# CAAint.net
KiCad netlist of a schematic drawn in EAGLE
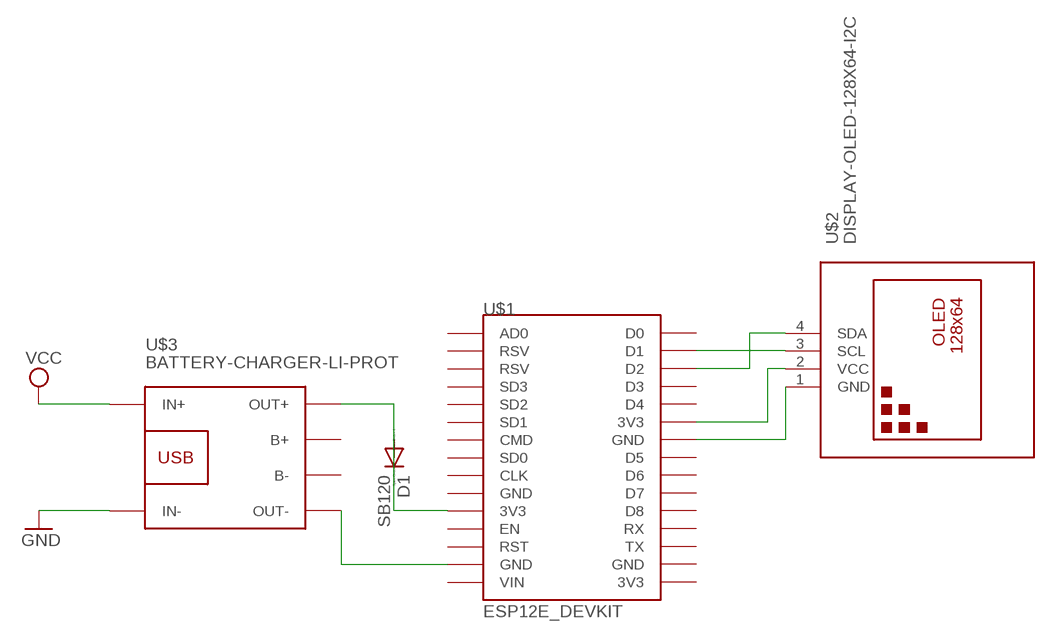
[diagram p0: schematic, sheet 1]

(export (version "E")
  (design (tool "Eeschema 10.0.6"))
  (components
    (comp (ref "D1")
      (value "SB120")
      (footprint "eagle-import:DO41-10")
      (libsource (lib "eagle-import") (part "SB120"))
    )
    (comp (ref "U$1")
      (value "ESP12E_DEVKIT")
      (footprint "eagle-import:ESP12E_DEVKIT")
      (libsource (lib "eagle-import") (part "ESP12E_DEVKIT"))
    )
    (comp (ref "U$2")
      (value "DISPLAY-OLED-128X64-I2C")
      (footprint "eagle-import:DISPLAY-OLED-128X64-I2C")
      (libsource (lib "eagle-import") (part "DISPLAY-OLED-128X64-I2C"))
    )
    (comp (ref "U$3")
      (value "BATTERY-CHARGER-LI-PROT")
      (footprint "eagle-import:BATTERY-CHARGER-LI-PROT")
      (libsource (lib "eagle-import") (part "BATTERY-CHARGER-LI-PROT"))
    )
  )
  (nets
    (net (code "1") (name "GND") (class "Default")
      (node (ref "U$1") (pin "GND@1") (pinfunction "GND_GND@1") (pintype "bidirectional"))
      (node (ref "U$1") (pin "GND@2") (pinfunction "GND_GND@2") (pintype "bidirectional"))
      (node (ref "U$2") (pin "1") (pinfunction "GND_1") (pintype "power_in"))
      (node (ref "U$3") (pin "IN-") (pinfunction "IN-_IN-") (pintype "bidirectional"))
      (node (ref "U$3") (pin "OUT-") (pinfunction "OUT-_OUT-") (pintype "bidirectional"))
    )
    (net (code "2") (name "Net-(D1-PadA)") (class "Default")
      (node (ref "D1") (pin "A") (pinfunction "A_A") (pintype "passive"))
      (node (ref "U$1") (pin "3V3@0") (pinfunction "3V3_3V3@0") (pintype "bidirectional"))
    )
    (net (code "3") (name "Net-(D1-PadC)") (class "Default")
      (node (ref "D1") (pin "C") (pinfunction "C_C") (pintype "passive"))
      (node (ref "U$3") (pin "OUT+") (pinfunction "OUT+_OUT+") (pintype "bidirectional"))
    )
    (net (code "4") (name "Net-(U$2-SCL)") (class "Default")
      (node (ref "U$1") (pin "D1") (pinfunction "D1_D1") (pintype "bidirectional"))
      (node (ref "U$2") (pin "3") (pinfunction "SCL_3") (pintype "bidirectional"))
    )
    (net (code "5") (name "Net-(U$2-SDA)") (class "Default")
      (node (ref "U$1") (pin "D2") (pinfunction "D2_D2") (pintype "bidirectional"))
      (node (ref "U$2") (pin "4") (pinfunction "SDA_4") (pintype "bidirectional"))
    )
    (net (code "6") (name "Net-(U$2-VCC)") (class "Default")
      (node (ref "U$1") (pin "3V3@1") (pinfunction "3V3_3V3@1") (pintype "bidirectional"))
      (node (ref "U$2") (pin "2") (pinfunction "VCC_2") (pintype "power_in"))
    )
    (net (code "7") (name "VCC") (class "Default")
      (node (ref "U$3") (pin "IN+") (pinfunction "IN+_IN+") (pintype "bidirectional"))
    )
    (net (code "8") (name "unconnected-(U$1-3V3-Pad3V3@2)") (class "Default")
      (node (ref "U$1") (pin "3V3@2") (pinfunction "3V3_3V3@2") (pintype "bidirectional"))
    )
    (net (code "9") (name "unconnected-(U$1-GND-PadGND@0)") (class "Default")
      (node (ref "U$1") (pin "GND@0") (pinfunction "GND_GND@0") (pintype "bidirectional"))
    )
    (net (code "10") (name "unconnected-(U$1-GND-PadGND@3)") (class "Default")
      (node (ref "U$1") (pin "GND@3") (pinfunction "GND_GND@3") (pintype "bidirectional"))
    )
    (net (code "11") (name "unconnected-(U$1-PadAD0)") (class "Default")
      (node (ref "U$1") (pin "AD0") (pinfunction "AD0_AD0") (pintype "bidirectional"))
    )
    (net (code "12") (name "unconnected-(U$1-PadCLK)") (class "Default")
      (node (ref "U$1") (pin "CLK") (pinfunction "CLK_CLK") (pintype "bidirectional"))
    )
    (net (code "13") (name "unconnected-(U$1-PadCMD)") (class "Default")
      (node (ref "U$1") (pin "CMD") (pinfunction "CMD_CMD") (pintype "bidirectional"))
    )
    (net (code "14") (name "unconnected-(U$1-PadD0)") (class "Default")
      (node (ref "U$1") (pin "D0") (pinfunction "D0_D0") (pintype "bidirectional"))
    )
    (net (code "15") (name "unconnected-(U$1-PadD3)") (class "Default")
      (node (ref "U$1") (pin "D3") (pinfunction "D3_D3") (pintype "bidirectional"))
    )
    (net (code "16") (name "unconnected-(U$1-PadD4)") (class "Default")
      (node (ref "U$1") (pin "D4") (pinfunction "D4_D4") (pintype "bidirectional"))
    )
    (net (code "17") (name "unconnected-(U$1-PadD5)") (class "Default")
      (node (ref "U$1") (pin "D5") (pinfunction "D5_D5") (pintype "bidirectional"))
    )
    (net (code "18") (name "unconnected-(U$1-PadD6)") (class "Default")
      (node (ref "U$1") (pin "D6") (pinfunction "D6_D6") (pintype "bidirectional"))
    )
    (net (code "19") (name "unconnected-(U$1-PadD7)") (class "Default")
      (node (ref "U$1") (pin "D7") (pinfunction "D7_D7") (pintype "bidirectional"))
    )
    (net (code "20") (name "unconnected-(U$1-PadD8)") (class "Default")
      (node (ref "U$1") (pin "D8") (pinfunction "D8_D8") (pintype "bidirectional"))
    )
    (net (code "21") (name "unconnected-(U$1-PadEN)") (class "Default")
      (node (ref "U$1") (pin "EN") (pinfunction "EN_EN") (pintype "bidirectional"))
    )
    (net (code "22") (name "unconnected-(U$1-PadRST)") (class "Default")
      (node (ref "U$1") (pin "RST") (pinfunction "RST_RST") (pintype "bidirectional"))
    )
    (net (code "23") (name "unconnected-(U$1-PadRX)") (class "Default")
      (node (ref "U$1") (pin "RX") (pinfunction "RX_RX") (pintype "bidirectional"))
    )
    (net (code "24") (name "unconnected-(U$1-PadSD0)") (class "Default")
      (node (ref "U$1") (pin "SD0") (pinfunction "SD0_SD0") (pintype "bidirectional"))
    )
    (net (code "25") (name "unconnected-(U$1-PadSD1)") (class "Default")
      (node (ref "U$1") (pin "SD1") (pinfunction "SD1_SD1") (pintype "bidirectional"))
    )
    (net (code "26") (name "unconnected-(U$1-PadSD2)") (class "Default")
      (node (ref "U$1") (pin "SD2") (pinfunction "SD2_SD2") (pintype "bidirectional"))
    )
    (net (code "27") (name "unconnected-(U$1-PadSD3)") (class "Default")
      (node (ref "U$1") (pin "SD3") (pinfunction "SD3_SD3") (pintype "bidirectional"))
    )
    (net (code "28") (name "unconnected-(U$1-PadTX)") (class "Default")
      (node (ref "U$1") (pin "TX") (pinfunction "TX_TX") (pintype "bidirectional"))
    )
    (net (code "29") (name "unconnected-(U$1-PadVIN)") (class "Default")
      (node (ref "U$1") (pin "VIN") (pinfunction "VIN_VIN") (pintype "bidirectional"))
    )
    (net (code "30") (name "unconnected-(U$1-RSV-PadRSV@0)") (class "Default")
      (node (ref "U$1") (pin "RSV@0") (pinfunction "RSV_RSV@0") (pintype "bidirectional"))
    )
    (net (code "31") (name "unconnected-(U$1-RSV-PadRSV@1)") (class "Default")
      (node (ref "U$1") (pin "RSV@1") (pinfunction "RSV_RSV@1") (pintype "bidirectional"))
    )
    (net (code "32") (name "unconnected-(U$3-PadB+)") (class "Default")
      (node (ref "U$3") (pin "B+") (pinfunction "B+_B+") (pintype "bidirectional"))
    )
    (net (code "33") (name "unconnected-(U$3-PadB-)") (class "Default")
      (node (ref "U$3") (pin "B-") (pinfunction "B-_B-") (pintype "bidirectional"))
    )
  )
)
